# Buck_Converter_24V_5V.net
KiCad netlist of a schematic drawn in Altium Designer
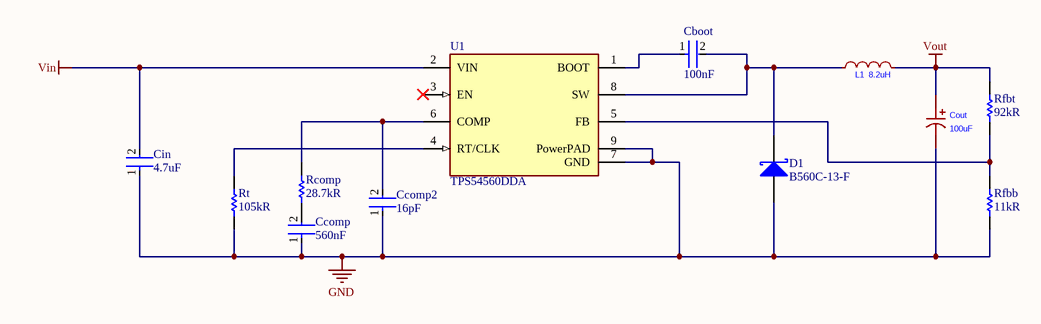
[diagram p0: Buck_Converter_24V_5V.SchDoc]

(export (version "E")
  (design (tool "Eeschema 10.0.6"))
  (components
    (comp (ref "Cboot")
      (value "100nF")
      (footprint "FP-CC0805-0_85-MFG")
      (description "CAP CER 0.1UF 50V X7R 0805")
      (fields (field (name "TOLERANCE") "0.1") (field (name "MANUFACTURER PART NUMBER") "CC0805KRX7R9BB104"))
      (libsource (lib "Altium Content Vault") (part "11868f565c42a9108669ba33697ecf6"))
    )
    (comp (ref "Ccomp")
      (value "560nF")
      (footprint "FP-CC0805-0_85-MFG")
      (description "CAP CER 0.1UF 50V X7R 0805")
      (fields (field (name "TOLERANCE") "0.1") (field (name "MANUFACTURER PART NUMBER") "CC0805KRX7R9BB104"))
      (libsource (lib "Altium Content Vault") (part "11868f565c42a9108669ba33697ecf6"))
    )
    (comp (ref "Ccomp2")
      (value "16pF")
      (footprint "FP-CC0805-0_85-MFG")
      (description "CAP CER 0.1UF 50V X7R 0805")
      (fields (field (name "TOLERANCE") "0.1") (field (name "MANUFACTURER PART NUMBER") "CC0805KRX7R9BB104"))
      (libsource (lib "Altium Content Vault") (part "11868f565c42a9108669ba33697ecf6"))
    )
    (comp (ref "Cin")
      (value "4.7uF")
      (footprint "FP-CC0805-0_85-MFG")
      (description "CAP CER 0.1UF 50V X7R 0805")
      (fields (field (name "TOLERANCE") "0.1") (field (name "MANUFACTURER PART NUMBER") "CC0805KRX7R9BB104"))
      (libsource (lib "Altium Content Vault") (part "11868f565c42a9108669ba33697ecf6"))
    )
    (comp (ref "Cout")
      (value "100uF")
      (footprint "CAP-SMD_BD6.3-L6.6-W6.6-LS7.6-RD")
      (fields
        (field (name "MANUFACTURER") "ROQANG(容强)")
        (field (name "MANUFACTURER PART") "RVT1H101M0607")
        (field (name "TOLERANCE") "±20%")
      )
      (libsource (lib "RVT1H101M06071_RVT1H101M0607") (part "RVT1H101M0607"))
    )
    (comp (ref "D1")
      (value "B560C-13-F")
      (footprint "DIOD-B5X0C-2_M")
      (description "Schottky Barrier Rectifier, 5 A, 60 V, -55 to 125 degC, 2-Pin SMD, RoHS, Tape and Reel")
      (fields (field (name "MANUFACTURER") "DiodesIncorporated"))
      (libsource (lib "Altium Content Vault") (part "DSKY-KA-2"))
    )
    (comp (ref "L1")
      (value "8.2uH")
      (footprint "IND-SMD_L7.0-W6.6_FXL0630")
      (fields
        (field (name "MANUFACTURER") "cjiang(长江微电)")
        (field (name "MANUFACTURER PART") "FXL0630-8R2-M")
        (field (name "TOLERANCE") "±20%")
      )
      (libsource (lib "FXL0630-8R2-M1_FXL0630-8R2-M") (part "FXL0630-8R2-M"))
    )
    (comp (ref "Rcomp")
      (value "28.7kR")
      (footprint "RESC1609X50X30NL8T20")
      (description "Chip Resistor, 10 KOhm, +/- 1%, 100 mW, -55 to 155 degC, 0603 (1608 Metric), RoHS, Tape and Reel")
      (fields (field (name "MANUFACTURER") "Vishay Semiconductor"))
      (libsource (lib "Altium Content Vault") (part "RES-2"))
    )
    (comp (ref "Rfbb")
      (value "11kR")
      (footprint "RESC1609X50X30NL8T20")
      (description "Chip Resistor, 10 KOhm, +/- 1%, 100 mW, -55 to 155 degC, 0603 (1608 Metric), RoHS, Tape and Reel")
      (fields (field (name "MANUFACTURER") "Vishay Semiconductor"))
      (libsource (lib "Altium Content Vault") (part "RES-2"))
    )
    (comp (ref "Rfbt")
      (value "92kR")
      (footprint "RESC2013X50X30LL20T20")
      (fields (field (name "MANUFACTURER") "Vishay Dale") (field (name "PART NUMBER") "CRCW08050000Z0EA"))
      (libsource (lib "Altium Content Vault") (part "RES"))
    )
    (comp (ref "Rt")
      (value "105kR")
      (footprint "RESC1609X50X30NL8T20")
      (description "Chip Resistor, 10 KOhm, +/- 1%, 100 mW, -55 to 155 degC, 0603 (1608 Metric), RoHS, Tape and Reel")
      (fields (field (name "MANUFACTURER") "Vishay Semiconductor"))
      (libsource (lib "Altium Content Vault") (part "RES-2"))
    )
    (comp (ref "U1")
      (value "TPS54560DDA")
      (footprint "FP-DDA0008E-MFG")
      (description "IC REG BCK SPLIT RAIL ADJ 8SOPWR")
      (fields
        (field (name "OCTOPART") "https://octopart.com/tps54560dda-texas+instruments-26977150")
        (field (name "MANUFACTURER") "Texas Instruments")
      )
      (libsource (lib "Altium Content Vault") (part "92fa32c5fb0b456cc3a934f0e7b6d8f"))
    )
  )
  (nets
    (net (code "1") (name "GND") (class "Default")
      (node (ref "Ccomp") (pin "1") (pinfunction "1_1") (pintype "passive"))
      (node (ref "Ccomp2") (pin "1") (pinfunction "1_1") (pintype "passive"))
      (node (ref "Cin") (pin "1") (pinfunction "1_1") (pintype "passive"))
      (node (ref "Cout") (pin "2") (pinfunction "2_2") (pintype "passive"))
      (node (ref "D1") (pin "2") (pinfunction "A_2") (pintype "passive"))
      (node (ref "Rfbb") (pin "1") (pinfunction "1_1") (pintype "passive"))
      (node (ref "Rt") (pin "1") (pinfunction "1_1") (pintype "passive"))
      (node (ref "U1") (pin "7") (pinfunction "GND_7") (pintype "power_in"))
      (node (ref "U1") (pin "9") (pinfunction "PowerPAD_9") (pintype "power_in"))
    )
    (net (code "2") (name "Net-(Ccomp-Pad2)") (class "Default")
      (node (ref "Ccomp") (pin "2") (pinfunction "2_2") (pintype "passive"))
      (node (ref "Rcomp") (pin "1") (pinfunction "1_1") (pintype "passive"))
    )
    (net (code "3") (name "Net-(D1-K)") (class "Default")
      (node (ref "Cboot") (pin "2") (pinfunction "2_2") (pintype "passive"))
      (node (ref "D1") (pin "1") (pinfunction "K_1") (pintype "passive"))
      (node (ref "L1") (pin "1") (pinfunction "1_1") (pintype "passive"))
      (node (ref "U1") (pin "8") (pinfunction "SW_8") (pintype "passive"))
    )
    (net (code "4") (name "Net-(U1-BOOT)") (class "Default")
      (node (ref "Cboot") (pin "1") (pinfunction "1_1") (pintype "passive"))
      (node (ref "U1") (pin "1") (pinfunction "BOOT_1") (pintype "passive"))
    )
    (net (code "5") (name "Net-(U1-COMP)") (class "Default")
      (node (ref "Ccomp2") (pin "2") (pinfunction "2_2") (pintype "passive"))
      (node (ref "Rcomp") (pin "2") (pinfunction "2_2") (pintype "passive"))
      (node (ref "U1") (pin "6") (pinfunction "COMP_6") (pintype "passive"))
    )
    (net (code "6") (name "Net-(U1-FB)") (class "Default")
      (node (ref "Rfbb") (pin "2") (pinfunction "2_2") (pintype "passive"))
      (node (ref "Rfbt") (pin "1") (pinfunction "1_1") (pintype "passive"))
      (node (ref "U1") (pin "5") (pinfunction "FB_5") (pintype "passive"))
    )
    (net (code "7") (name "Net-(U1-RT{slash}CLK)") (class "Default")
      (node (ref "Rt") (pin "2") (pinfunction "2_2") (pintype "passive"))
      (node (ref "U1") (pin "4") (pinfunction "RT/CLK_4") (pintype "input"))
    )
    (net (code "8") (name "Vin") (class "Default")
      (node (ref "Cin") (pin "2") (pinfunction "2_2") (pintype "passive"))
      (node (ref "U1") (pin "2") (pinfunction "VIN_2") (pintype "power_in"))
    )
    (net (code "9") (name "Vout") (class "Default")
      (node (ref "Cout") (pin "1") (pinfunction "1_1") (pintype "passive"))
      (node (ref "L1") (pin "2") (pinfunction "2_2") (pintype "passive"))
      (node (ref "Rfbt") (pin "2") (pinfunction "2_2") (pintype "passive"))
    )
    (net (code "10") (name "unconnected-(U1-EN-Pad3)") (class "Default")
      (node (ref "U1") (pin "3") (pinfunction "EN_3") (pintype "input+no_connect"))
    )
  )
)
